# k1fm-gps-breakout.net
KiCad netlist of a schematic drawn in EAGLE
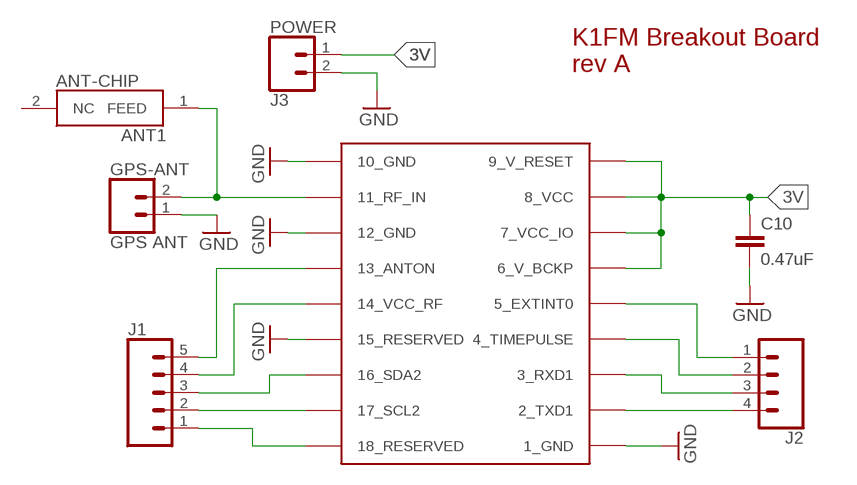
[diagram p0: schematic, sheet 1]

(export (version "E")
  (design (tool "Eeschema 10.0.6"))
  (components
    (comp (ref "ANT-CHIP")
      (value "ANT1")
      (footprint "eagle-import:1575AT43A0040E")
      (fields
        (field (name "MANUFACTURER_PART_NUMBER") "1575AT43A0040E")
        (field (name "MOUSER_PART_NUMBER") "609-1575AT43A0040E")
      )
      (libsource (lib "eagle-import") (part "1575AT43A0040E"))
    )
    (comp (ref "C10")
      (value "0.47uF")
      (footprint "eagle-import:0603")
      (libsource (lib "eagle-import") (part "0.1UF-0603-25V-5%"))
    )
    (comp (ref "GPS-ANT")
      (value "GPS ANT")
      (footprint "eagle-import:1X02")
      (libsource (lib "eagle-import") (part "CONN_02"))
    )
    (comp (ref "GPS1")
      (value "UBLOX_MAX")
      (footprint "eagle-import:UBLOX_MAX")
      (libsource (lib "eagle-import") (part "UBLOX_MAX"))
    )
    (comp (ref "J1")
      (value "CONN_05")
      (footprint "eagle-import:1X05")
      (libsource (lib "eagle-import") (part "CONN_05"))
    )
    (comp (ref "J2")
      (value "CONN_04")
      (footprint "eagle-import:1X04")
      (libsource (lib "eagle-import") (part "CONN_04"))
    )
    (comp (ref "J3")
      (value "POWER")
      (footprint "eagle-import:1X02")
      (libsource (lib "eagle-import") (part "CONN_02"))
    )
  )
  (nets
    (net (code "1") (name "3V") (class "Default")
      (node (ref "C10") (pin "1") (pinfunction "1_1") (pintype "passive"))
      (node (ref "GPS1") (pin "6_V_BCKP") (pinfunction "6_V_BCKP_6_V_BCKP") (pintype "bidirectional"))
      (node (ref "GPS1") (pin "7_VCC_IO") (pinfunction "7_VCC_IO_7_VCC_IO") (pintype "power_in"))
      (node (ref "GPS1") (pin "8_VCC") (pinfunction "8_VCC_8_VCC") (pintype "power_in"))
      (node (ref "GPS1") (pin "9_V_RESET") (pinfunction "9_V_RESET_9_V_RESET") (pintype "power_in"))
      (node (ref "J3") (pin "1") (pinfunction "1_1") (pintype "passive"))
    )
    (net (code "2") (name "GND") (class "Default")
      (node (ref "C10") (pin "2") (pinfunction "2_2") (pintype "passive"))
      (node (ref "GPS-ANT") (pin "1") (pinfunction "1_1") (pintype "passive"))
      (node (ref "GPS1") (pin "10_GND") (pinfunction "10_GND_10_GND") (pintype "power_in"))
      (node (ref "GPS1") (pin "12_GND") (pinfunction "12_GND_12_GND") (pintype "power_in"))
      (node (ref "GPS1") (pin "15_RESERVED") (pinfunction "15_RESERVED_15_RESERVED") (pintype "bidirectional"))
      (node (ref "GPS1") (pin "1_GND") (pinfunction "1_GND_1_GND") (pintype "power_in"))
      (node (ref "J3") (pin "2") (pinfunction "2_2") (pintype "passive"))
    )
    (net (code "3") (name "Net-(ANT-CHIP-FEED)") (class "Default")
      (node (ref "ANT-CHIP") (pin "1") (pinfunction "FEED_1") (pintype "input"))
      (node (ref "GPS-ANT") (pin "2") (pinfunction "2_2") (pintype "passive"))
      (node (ref "GPS1") (pin "11_RF_IN") (pinfunction "11_RF_IN_11_RF_IN") (pintype "bidirectional"))
    )
    (net (code "4") (name "Net-(GPS1-Pad2_TXD1)") (class "Default")
      (node (ref "GPS1") (pin "2_TXD1") (pinfunction "2_TXD1_2_TXD1") (pintype "bidirectional"))
      (node (ref "J2") (pin "4") (pinfunction "4_4") (pintype "passive"))
    )
    (net (code "5") (name "Net-(GPS1-Pad3_RXD1)") (class "Default")
      (node (ref "GPS1") (pin "3_RXD1") (pinfunction "3_RXD1_3_RXD1") (pintype "bidirectional"))
      (node (ref "J2") (pin "3") (pinfunction "3_3") (pintype "passive"))
    )
    (net (code "6") (name "Net-(GPS1-Pad4_TIMEPULSE)") (class "Default")
      (node (ref "GPS1") (pin "4_TIMEPULSE") (pinfunction "4_TIMEPULSE_4_TIMEPULSE") (pintype "bidirectional"))
      (node (ref "J2") (pin "2") (pinfunction "2_2") (pintype "passive"))
    )
    (net (code "7") (name "Net-(GPS1-Pad5_EXTINT0)") (class "Default")
      (node (ref "GPS1") (pin "5_EXTINT0") (pinfunction "5_EXTINT0_5_EXTINT0") (pintype "bidirectional"))
      (node (ref "J2") (pin "1") (pinfunction "1_1") (pintype "passive"))
    )
    (net (code "8") (name "Net-(GPS1-Pad13_ANTON)") (class "Default")
      (node (ref "GPS1") (pin "13_ANTON") (pinfunction "13_ANTON_13_ANTON") (pintype "bidirectional"))
      (node (ref "J1") (pin "5") (pinfunction "5_5") (pintype "passive"))
    )
    (net (code "9") (name "Net-(GPS1-Pad14_VCC_RF)") (class "Default")
      (node (ref "GPS1") (pin "14_VCC_RF") (pinfunction "14_VCC_RF_14_VCC_RF") (pintype "bidirectional"))
      (node (ref "J1") (pin "4") (pinfunction "4_4") (pintype "passive"))
    )
    (net (code "10") (name "Net-(GPS1-Pad16_SDA2)") (class "Default")
      (node (ref "GPS1") (pin "16_SDA2") (pinfunction "16_SDA2_16_SDA2") (pintype "bidirectional"))
      (node (ref "J1") (pin "3") (pinfunction "3_3") (pintype "passive"))
    )
    (net (code "11") (name "Net-(GPS1-Pad17_SCL2)") (class "Default")
      (node (ref "GPS1") (pin "17_SCL2") (pinfunction "17_SCL2_17_SCL2") (pintype "bidirectional"))
      (node (ref "J1") (pin "2") (pinfunction "2_2") (pintype "passive"))
    )
    (net (code "12") (name "Net-(GPS1-Pad18_RESERVED)") (class "Default")
      (node (ref "GPS1") (pin "18_RESERVED") (pinfunction "18_RESERVED_18_RESERVED") (pintype "bidirectional"))
      (node (ref "J1") (pin "1") (pinfunction "1_1") (pintype "passive"))
    )
    (net (code "13") (name "unconnected-(ANT-CHIP-NC-Pad2)") (class "Default")
      (node (ref "ANT-CHIP") (pin "2") (pinfunction "NC_2") (pintype "no_connect"))
    )
  )
)
